# pc_healthypi_move_bottom_pcb_v2.net
KiCad netlist of a schematic drawn in EAGLE
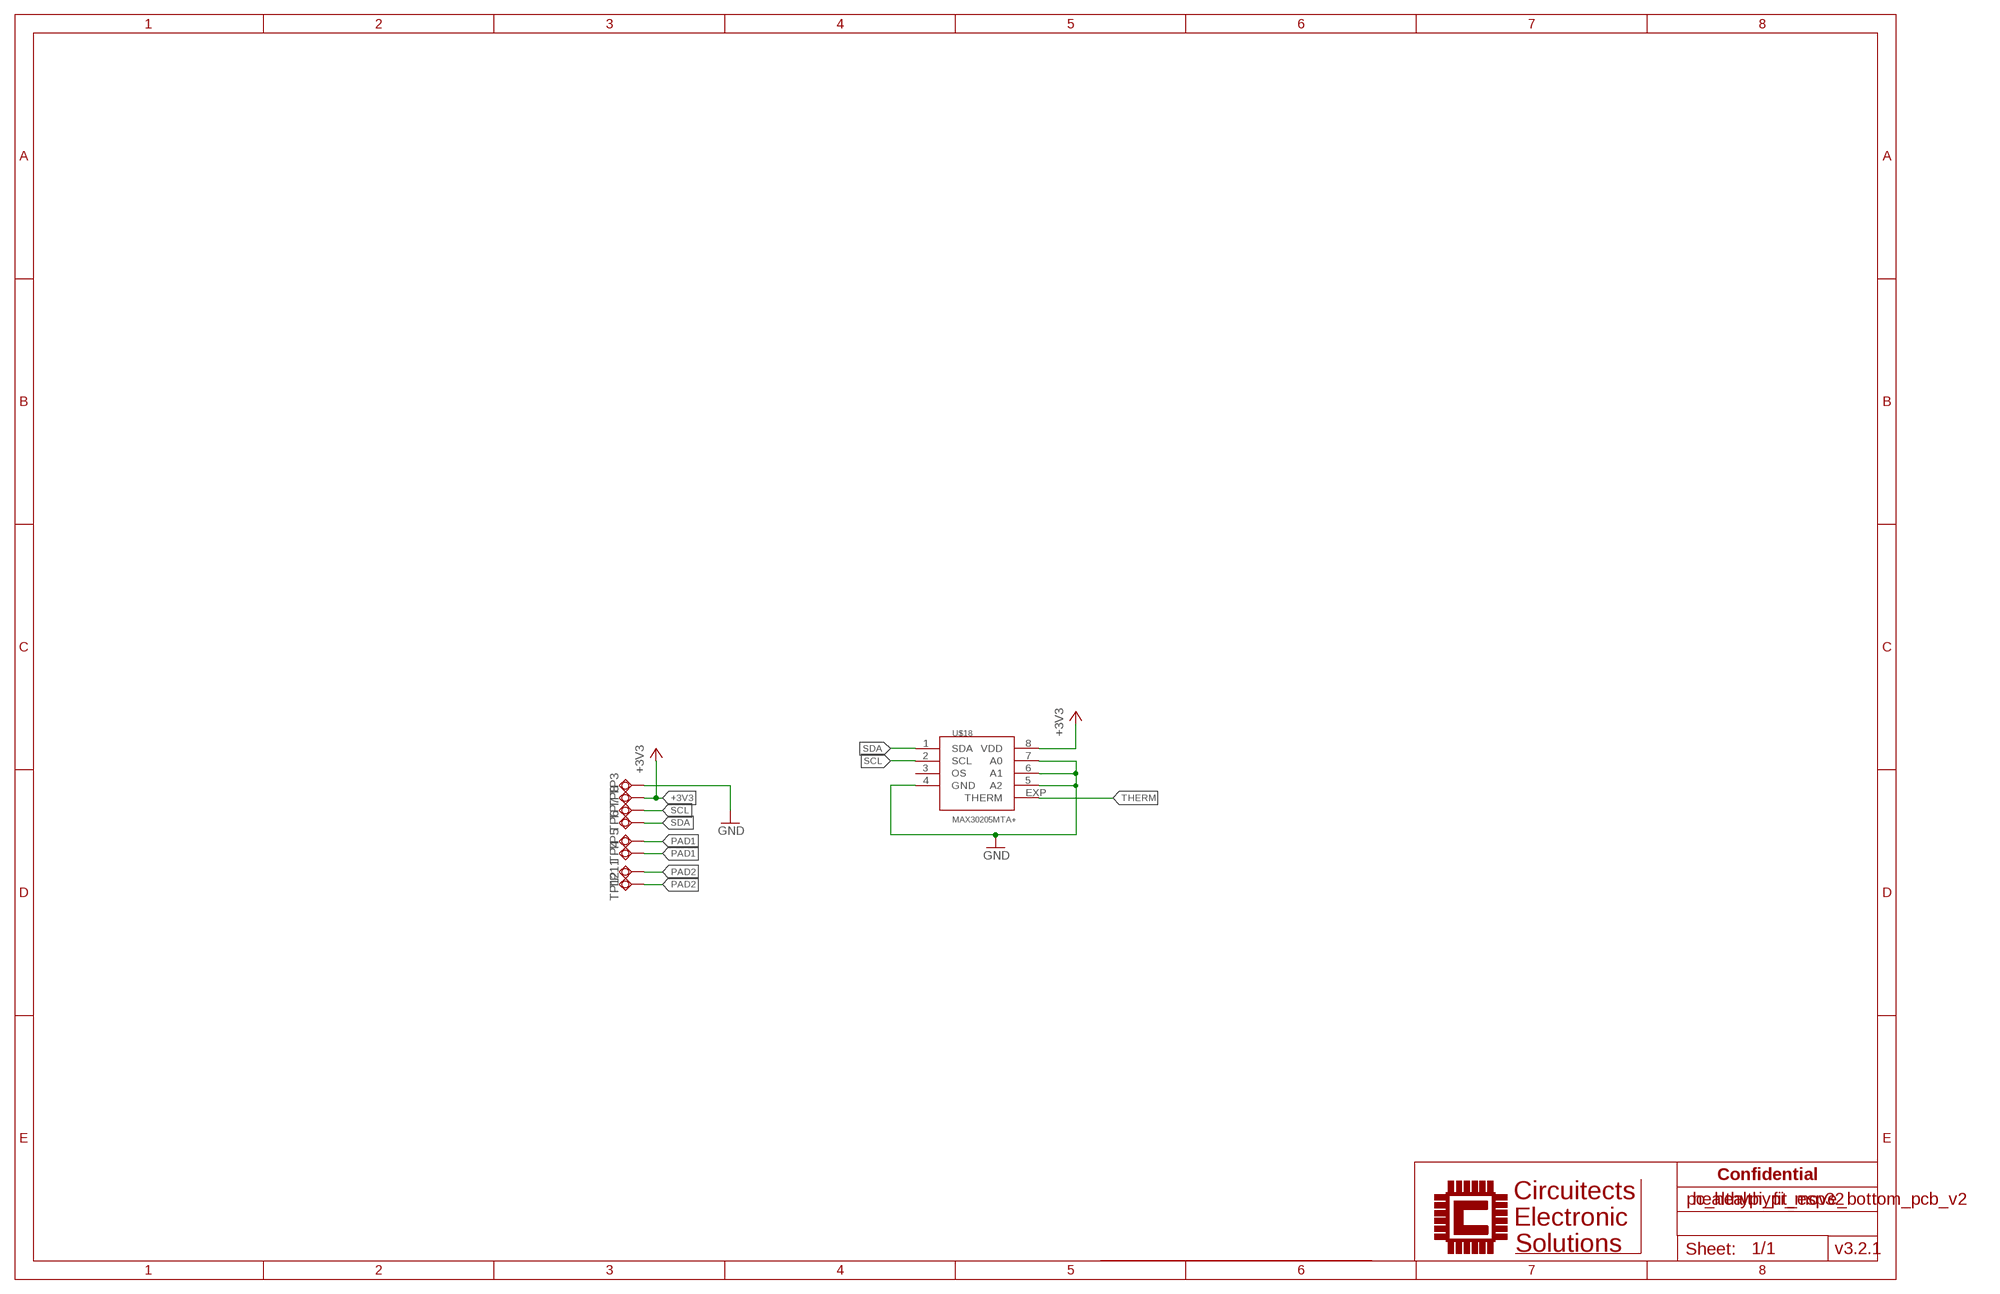
[diagram p0: schematic, sheet 1]

(export (version "E")
  (design (tool "Eeschema 10.0.6"))
  (components
    (comp (ref "TP3")
      (value "TPSQTP20SQ")
      (footprint "eagle-import:TP20SQ")
      (libsource (lib "eagle-import") (part "TPSQTP20SQ"))
    )
    (comp (ref "TP4")
      (value "TPSQTP20SQ")
      (footprint "eagle-import:TP20SQ")
      (libsource (lib "eagle-import") (part "TPSQTP20SQ"))
    )
    (comp (ref "TP5")
      (value "TPSQTP20SQ")
      (footprint "eagle-import:TP20SQ")
      (libsource (lib "eagle-import") (part "TPSQTP20SQ"))
    )
    (comp (ref "TP6")
      (value "TPSQTP20SQ")
      (footprint "eagle-import:TP20SQ")
      (libsource (lib "eagle-import") (part "TPSQTP20SQ"))
    )
    (comp (ref "TP7")
      (value "TPSQTP20SQ")
      (footprint "eagle-import:TP20SQ")
      (libsource (lib "eagle-import") (part "TPSQTP20SQ"))
    )
    (comp (ref "TP8")
      (value "TPSQTP20SQ")
      (footprint "eagle-import:TP20SQ")
      (libsource (lib "eagle-import") (part "TPSQTP20SQ"))
    )
    (comp (ref "TP11")
      (value "TPSQTP20SQ")
      (footprint "eagle-import:TP20SQ")
      (libsource (lib "eagle-import") (part "TPSQTP20SQ"))
    )
    (comp (ref "TP12")
      (value "TPSQTP20SQ")
      (footprint "eagle-import:TP20SQ")
      (libsource (lib "eagle-import") (part "TPSQTP20SQ"))
    )
    (comp (ref "U$18")
      (value "MAX30205MTA+")
      (footprint "eagle-import:TDFN-08")
      (libsource (lib "eagle-import") (part "MAX30205MTA+"))
    )
  )
  (nets
    (net (code "1") (name "+3V3") (class "Default")
      (node (ref "TP8") (pin "TP") (pinfunction "TP_TP") (pintype "input"))
      (node (ref "U$18") (pin "8") (pinfunction "VDD_8") (pintype "bidirectional"))
    )
    (net (code "2") (name "GND") (class "Default")
      (node (ref "TP3") (pin "TP") (pinfunction "TP_TP") (pintype "input"))
      (node (ref "U$18") (pin "4") (pinfunction "GND_4") (pintype "bidirectional"))
      (node (ref "U$18") (pin "5") (pinfunction "A2_5") (pintype "bidirectional"))
      (node (ref "U$18") (pin "6") (pinfunction "A1_6") (pintype "bidirectional"))
      (node (ref "U$18") (pin "7") (pinfunction "A0_7") (pintype "bidirectional"))
    )
    (net (code "3") (name "PAD1") (class "Default")
      (node (ref "TP4") (pin "TP") (pinfunction "TP_TP") (pintype "input"))
      (node (ref "TP5") (pin "TP") (pinfunction "TP_TP") (pintype "input"))
    )
    (net (code "4") (name "PAD2") (class "Default")
      (node (ref "TP11") (pin "TP") (pinfunction "TP_TP") (pintype "input"))
      (node (ref "TP12") (pin "TP") (pinfunction "TP_TP") (pintype "input"))
    )
    (net (code "5") (name "SCL") (class "Default")
      (node (ref "TP7") (pin "TP") (pinfunction "TP_TP") (pintype "input"))
      (node (ref "U$18") (pin "2") (pinfunction "SCL_2") (pintype "bidirectional"))
    )
    (net (code "6") (name "SDA") (class "Default")
      (node (ref "TP6") (pin "TP") (pinfunction "TP_TP") (pintype "input"))
      (node (ref "U$18") (pin "1") (pinfunction "SDA_1") (pintype "bidirectional"))
    )
    (net (code "7") (name "THERM") (class "Default")
      (node (ref "U$18") (pin "EXP") (pinfunction "THERM_EXP") (pintype "bidirectional"))
    )
    (net (code "8") (name "unconnected-(U$18-OS-Pad3)") (class "Default")
      (node (ref "U$18") (pin "3") (pinfunction "OS_3") (pintype "bidirectional"))
    )
  )
)
